# LFR_Body_Circuit.net
KiCad netlist of a schematic drawn in EasyEDA
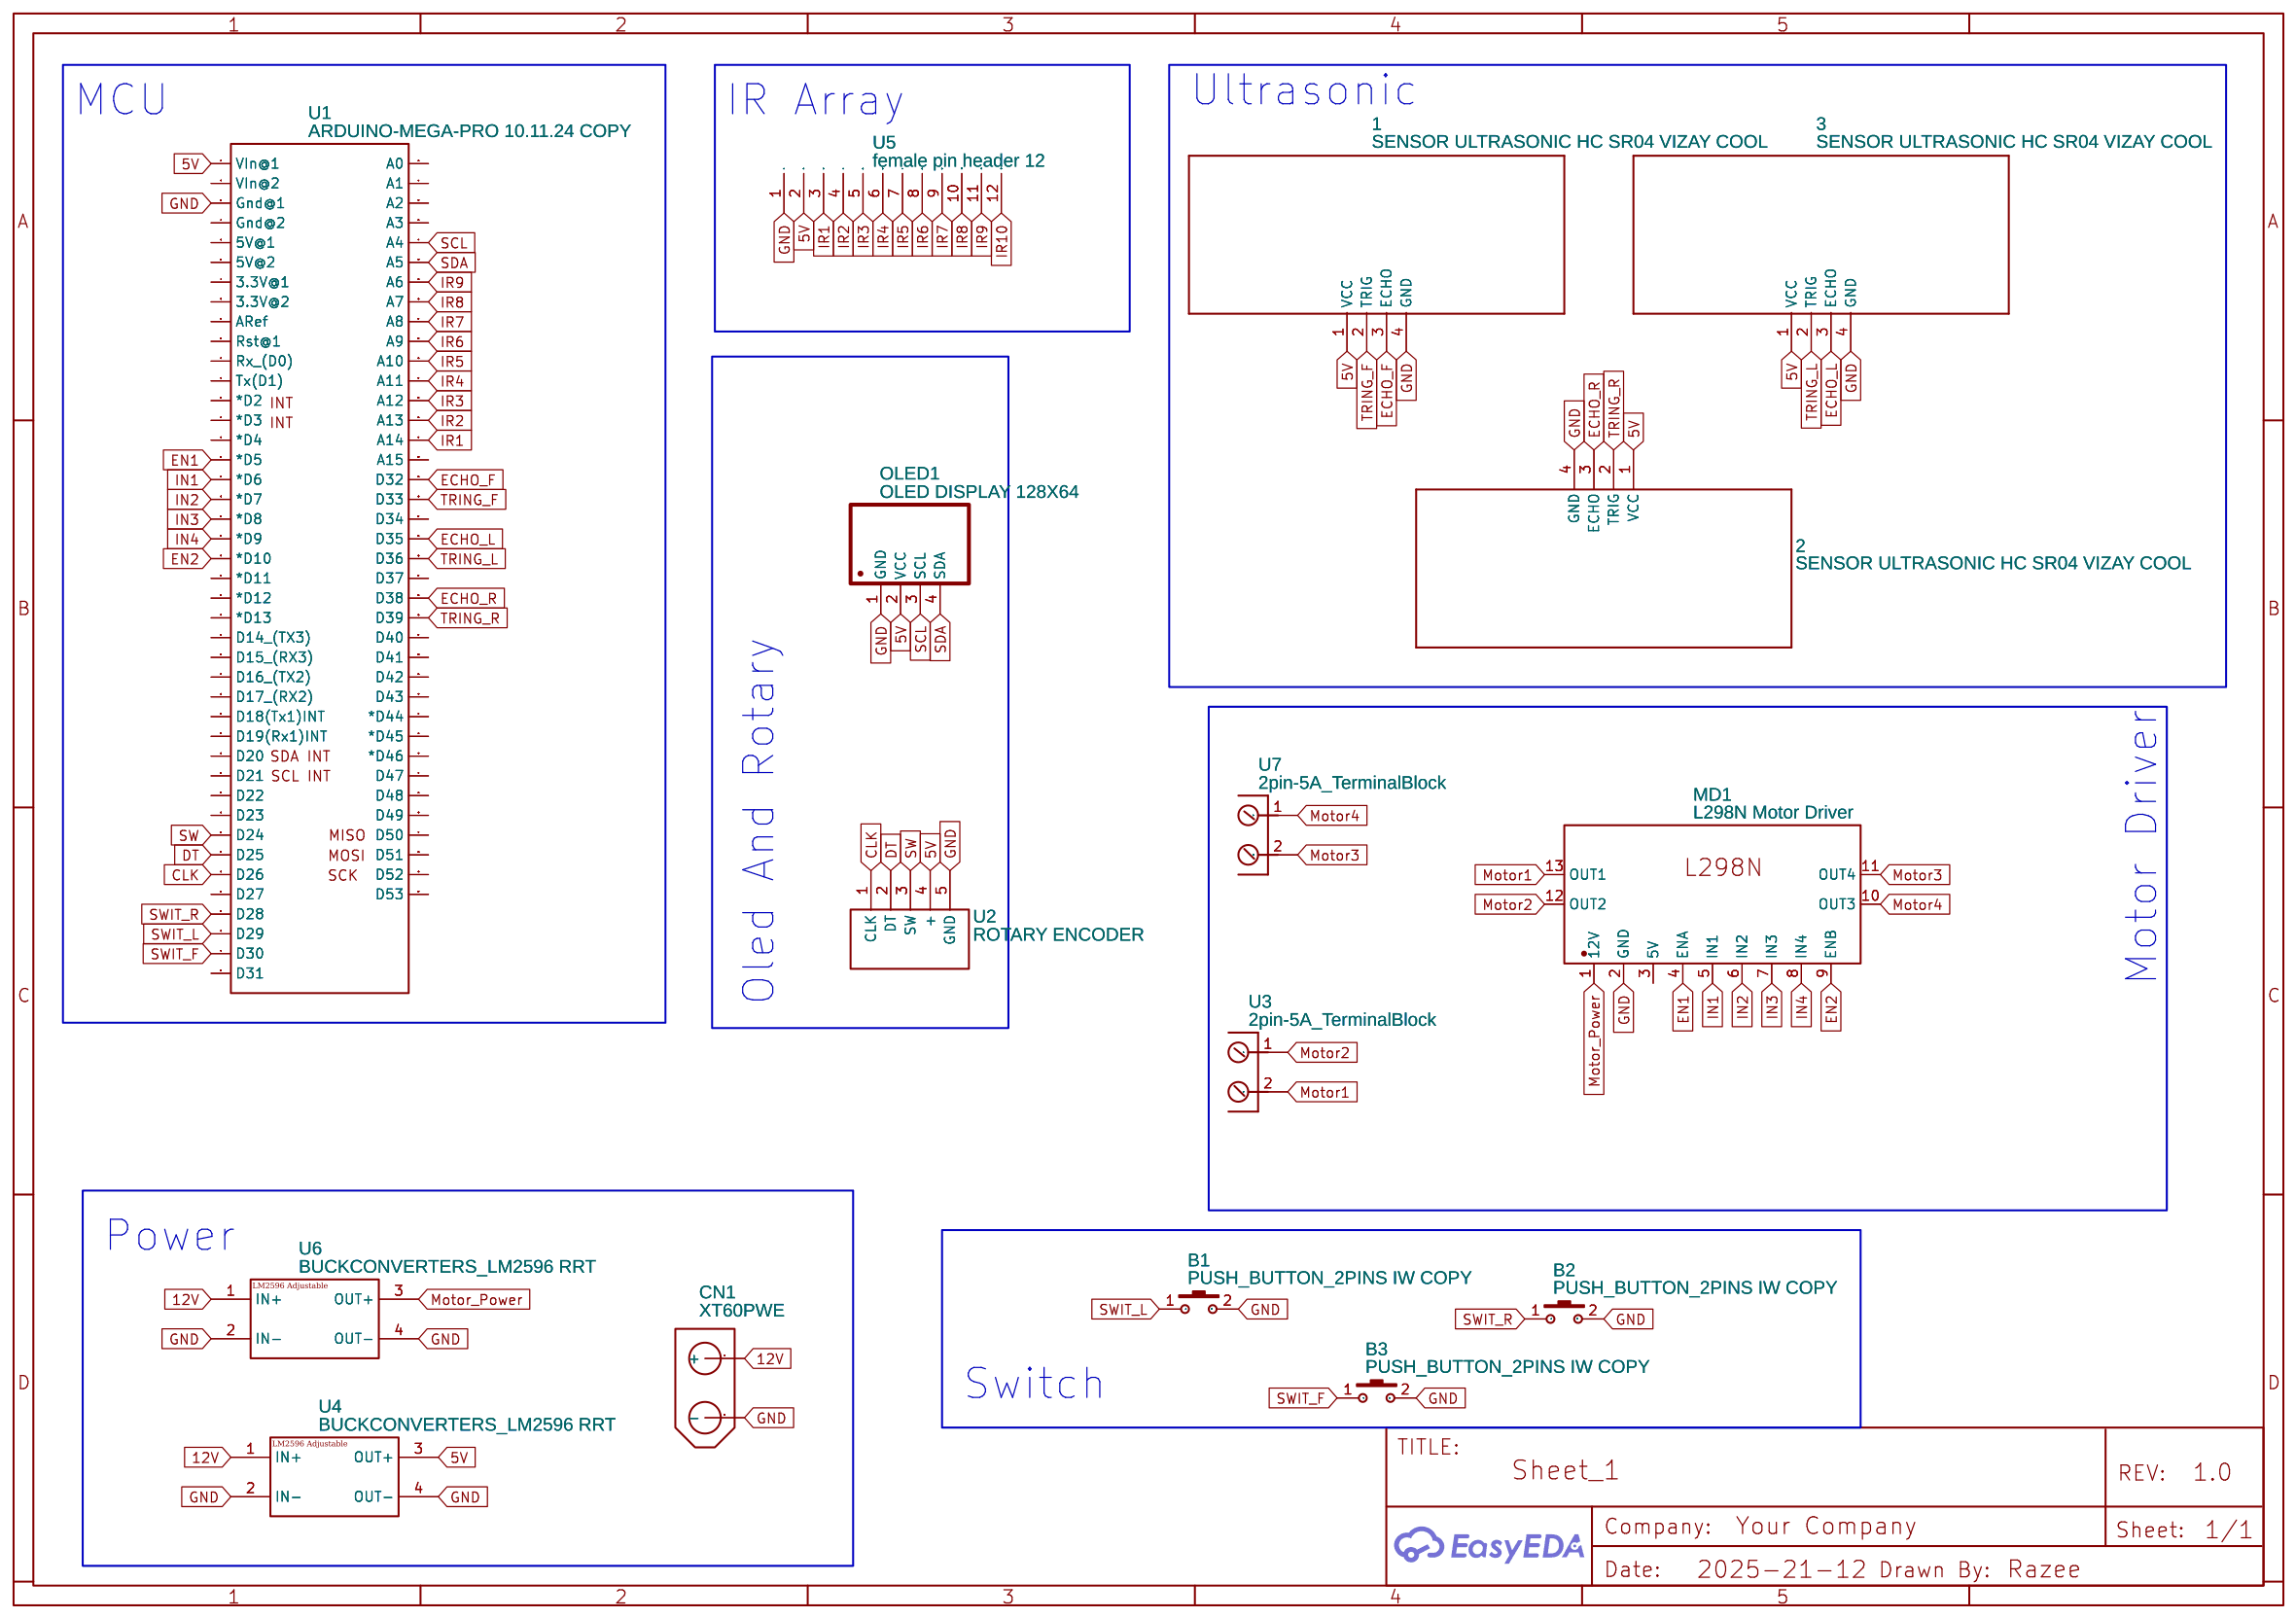
[diagram p0: schematic sheet]

(export (version "E")
  (design (tool "Eeschema 10.0.6"))
  (components
    (comp (ref "1")
      (value "SENSOR ULTRASONIC HC SR04 VIZAY COOL")
      (libsource (lib "") (part "SENSOR ULTRASONIC HC SR04 VIZAY COOL"))
    )
    (comp (ref "2")
      (value "SENSOR ULTRASONIC HC SR04 VIZAY COOL")
      (libsource (lib "") (part "SENSOR ULTRASONIC HC SR04 VIZAY COOL_1"))
    )
    (comp (ref "3")
      (value "SENSOR ULTRASONIC HC SR04 VIZAY COOL")
      (libsource (lib "") (part "SENSOR ULTRASONIC HC SR04 VIZAY COOL"))
    )
    (comp (ref "B1")
      (value "PUSH_BUTTON_2PINS IW COPY")
      (fields (field (name "Manufacturer Part") "PUSH_BUTTON_2Pini"))
      (libsource (lib "") (part "PUSH_BUTTON_2PINS IW COPY"))
    )
    (comp (ref "B2")
      (value "PUSH_BUTTON_2PINS IW COPY")
      (fields (field (name "Manufacturer Part") "PUSH_BUTTON_2Pini"))
      (libsource (lib "") (part "PUSH_BUTTON_2PINS IW COPY"))
    )
    (comp (ref "B3")
      (value "PUSH_BUTTON_2PINS IW COPY")
      (fields (field (name "Manufacturer Part") "PUSH_BUTTON_2Pini"))
      (libsource (lib "") (part "PUSH_BUTTON_2PINS IW COPY"))
    )
    (comp (ref "CN1")
      (value "XT60PWE")
      (fields (field (name "Manufacturer") "Changzhou Amass Elec"))
      (libsource (lib "") (part "XT60 COPY COPY"))
    )
    (comp (ref "MD1") (value "L298N Motor Driver") (libsource (lib "") (part "L298N Motor Driver")))
    (comp (ref "OLED1") (value "OLED DISPLAY 128X64") (libsource (lib "") (part "OLED DISPLAY 128X64")))
    (comp (ref "U1")
      (value "ARDUINO-MEGA-PRO 10.11.24 COPY")
      (fields (field (name "Manufacturer Part") "ARDUINO MEGA 2560 PRO EMBED"))
      (libsource (lib "") (part "ARDUINO-MEGA-PRO 10.11.24 COPY"))
    )
    (comp (ref "U2") (value "ROTARY ENCODER") (libsource (lib "") (part "ROTARY ENCODER")))
    (comp (ref "U3") (value "2pin-5A_TerminalBlock") (libsource (lib "") (part "2pin-5A_TerminalBlock")))
    (comp (ref "U4")
      (value "BUCKCONVERTERS_LM2596 RRT")
      (libsource (lib "") (part "BuckConverters_LM2596_Adj"))
    )
    (comp (ref "U5")
      (value "female pin header 12")
      (fields (field (name "Manufacturer Part") "New SchematicLib"))
      (libsource (lib "") (part "female pin header 12"))
    )
    (comp (ref "U6")
      (value "BUCKCONVERTERS_LM2596 RRT")
      (libsource (lib "") (part "BuckConverters_LM2596_Adj"))
    )
    (comp (ref "U7") (value "2pin-5A_TerminalBlock") (libsource (lib "") (part "2pin-5A_TerminalBlock")))
  )
  (nets
    (net (code "1") (name "5V") (class "Default")
      (node (ref "1") (pin "1") (pinfunction "VCC_1") (pintype "bidirectional"))
      (node (ref "2") (pin "1") (pinfunction "VCC_1") (pintype "bidirectional"))
      (node (ref "3") (pin "1") (pinfunction "VCC_1") (pintype "bidirectional"))
      (node (ref "OLED1") (pin "2") (pinfunction "VCC_2") (pintype "unspecified"))
      (node (ref "U1") (pin "1") (pinfunction "VIn@1_1") (pintype "unspecified"))
      (node (ref "U2") (pin "4") (pinfunction "+_4") (pintype "unspecified"))
      (node (ref "U4") (pin "3") (pinfunction "OUT+_3") (pintype "unspecified"))
      (node (ref "U5") (pin "2") (pinfunction "2_2") (pintype "unspecified"))
    )
    (net (code "2") (name "12V") (class "Default")
      (node (ref "CN1") (pin "1") (pinfunction "+_1") (pintype "unspecified"))
      (node (ref "U4") (pin "1") (pinfunction "IN+_1") (pintype "unspecified"))
      (node (ref "U6") (pin "1") (pinfunction "IN+_1") (pintype "unspecified"))
    )
    (net (code "3") (name "CLK") (class "Default")
      (node (ref "U1") (pin "37") (pinfunction "D26_37") (pintype "unspecified"))
      (node (ref "U2") (pin "1") (pinfunction "CLK_1") (pintype "unspecified"))
    )
    (net (code "4") (name "DT") (class "Default")
      (node (ref "U1") (pin "36") (pinfunction "D25_36") (pintype "unspecified"))
      (node (ref "U2") (pin "2") (pinfunction "DT_2") (pintype "unspecified"))
    )
    (net (code "5") (name "ECHO_F") (class "Default")
      (node (ref "1") (pin "3") (pinfunction "ECHO_3") (pintype "bidirectional"))
      (node (ref "U1") (pin "59") (pinfunction "D32_59") (pintype "unspecified"))
    )
    (net (code "6") (name "ECHO_L") (class "Default")
      (node (ref "3") (pin "3") (pinfunction "ECHO_3") (pintype "bidirectional"))
      (node (ref "U1") (pin "62") (pinfunction "D35_62") (pintype "unspecified"))
    )
    (net (code "7") (name "ECHO_R") (class "Default")
      (node (ref "2") (pin "3") (pinfunction "ECHO_3") (pintype "bidirectional"))
      (node (ref "U1") (pin "65") (pinfunction "D38_65") (pintype "unspecified"))
    )
    (net (code "8") (name "EN1") (class "Default")
      (node (ref "MD1") (pin "4") (pinfunction "ENA_4") (pintype "unspecified"))
      (node (ref "U1") (pin "16") (pinfunction "*D5_16") (pintype "unspecified"))
    )
    (net (code "9") (name "EN2") (class "Default")
      (node (ref "MD1") (pin "9") (pinfunction "ENB_9") (pintype "unspecified"))
      (node (ref "U1") (pin "21") (pinfunction "*D10_21") (pintype "unspecified"))
    )
    (net (code "10") (name "GND") (class "Default")
      (node (ref "1") (pin "4") (pinfunction "GND_4") (pintype "bidirectional"))
      (node (ref "2") (pin "4") (pinfunction "GND_4") (pintype "bidirectional"))
      (node (ref "3") (pin "4") (pinfunction "GND_4") (pintype "bidirectional"))
      (node (ref "B1") (pin "2") (pinfunction "2_2") (pintype "unspecified"))
      (node (ref "B2") (pin "2") (pinfunction "2_2") (pintype "unspecified"))
      (node (ref "B3") (pin "2") (pinfunction "2_2") (pintype "unspecified"))
      (node (ref "CN1") (pin "2") (pinfunction "-_2") (pintype "unspecified"))
      (node (ref "MD1") (pin "2") (pinfunction "GND_2") (pintype "unspecified"))
      (node (ref "OLED1") (pin "1") (pinfunction "GND_1") (pintype "unspecified"))
      (node (ref "U1") (pin "3") (pinfunction "Gnd@1_3") (pintype "unspecified"))
      (node (ref "U2") (pin "5") (pinfunction "GND_5") (pintype "unspecified"))
      (node (ref "U4") (pin "2") (pinfunction "IN-_2") (pintype "unspecified"))
      (node (ref "U4") (pin "4") (pinfunction "OUT-_4") (pintype "unspecified"))
      (node (ref "U5") (pin "1") (pinfunction "1_1") (pintype "unspecified"))
      (node (ref "U6") (pin "2") (pinfunction "IN-_2") (pintype "unspecified"))
      (node (ref "U6") (pin "4") (pinfunction "OUT-_4") (pintype "unspecified"))
    )
    (net (code "11") (name "IN1") (class "Default")
      (node (ref "MD1") (pin "5") (pinfunction "IN1_5") (pintype "unspecified"))
      (node (ref "U1") (pin "17") (pinfunction "*D6_17") (pintype "unspecified"))
    )
    (net (code "12") (name "IN2") (class "Default")
      (node (ref "MD1") (pin "6") (pinfunction "IN2_6") (pintype "unspecified"))
      (node (ref "U1") (pin "18") (pinfunction "*D7_18") (pintype "unspecified"))
    )
    (net (code "13") (name "IN3") (class "Default")
      (node (ref "MD1") (pin "7") (pinfunction "IN3_7") (pintype "unspecified"))
      (node (ref "U1") (pin "19") (pinfunction "*D8_19") (pintype "unspecified"))
    )
    (net (code "14") (name "IN4") (class "Default")
      (node (ref "MD1") (pin "8") (pinfunction "IN4_8") (pintype "unspecified"))
      (node (ref "U1") (pin "20") (pinfunction "*D9_20") (pintype "unspecified"))
    )
    (net (code "15") (name "IR1") (class "Default")
      (node (ref "U1") (pin "57") (pinfunction "A14_57") (pintype "unspecified"))
      (node (ref "U5") (pin "3") (pinfunction "3_3") (pintype "unspecified"))
    )
    (net (code "16") (name "IR2") (class "Default")
      (node (ref "U1") (pin "56") (pinfunction "A13_56") (pintype "unspecified"))
      (node (ref "U5") (pin "4") (pinfunction "4_4") (pintype "unspecified"))
    )
    (net (code "17") (name "IR3") (class "Default")
      (node (ref "U1") (pin "55") (pinfunction "A12_55") (pintype "unspecified"))
      (node (ref "U5") (pin "5") (pinfunction "5_5") (pintype "unspecified"))
    )
    (net (code "18") (name "IR4") (class "Default")
      (node (ref "U1") (pin "54") (pinfunction "A11_54") (pintype "unspecified"))
      (node (ref "U5") (pin "6") (pinfunction "6_6") (pintype "unspecified"))
    )
    (net (code "19") (name "IR5") (class "Default")
      (node (ref "U1") (pin "53") (pinfunction "A10_53") (pintype "unspecified"))
      (node (ref "U5") (pin "7") (pinfunction "7_7") (pintype "unspecified"))
    )
    (net (code "20") (name "IR6") (class "Default")
      (node (ref "U1") (pin "52") (pinfunction "A9_52") (pintype "unspecified"))
      (node (ref "U5") (pin "8") (pinfunction "8_8") (pintype "unspecified"))
    )
    (net (code "21") (name "IR7") (class "Default")
      (node (ref "U1") (pin "51") (pinfunction "A8_51") (pintype "unspecified"))
      (node (ref "U5") (pin "9") (pinfunction "9_9") (pintype "unspecified"))
    )
    (net (code "22") (name "IR8") (class "Default")
      (node (ref "U1") (pin "50") (pinfunction "A7_50") (pintype "unspecified"))
      (node (ref "U5") (pin "10") (pinfunction "10_10") (pintype "unspecified"))
    )
    (net (code "23") (name "IR9") (class "Default")
      (node (ref "U1") (pin "49") (pinfunction "A6_49") (pintype "unspecified"))
      (node (ref "U5") (pin "11") (pinfunction "11_11") (pintype "unspecified"))
    )
    (net (code "24") (name "IR10") (class "Default")
      (node (ref "U5") (pin "12") (pinfunction "12_12") (pintype "unspecified"))
    )
    (net (code "25") (name "Motor1") (class "Default")
      (node (ref "MD1") (pin "13") (pinfunction "OUT1_13") (pintype "unspecified"))
      (node (ref "U3") (pin "2") (pinfunction "2_2") (pintype "unspecified"))
    )
    (net (code "26") (name "Motor2") (class "Default")
      (node (ref "MD1") (pin "12") (pinfunction "OUT2_12") (pintype "unspecified"))
      (node (ref "U3") (pin "1") (pinfunction "1_1") (pintype "unspecified"))
    )
    (net (code "27") (name "Motor3") (class "Default")
      (node (ref "MD1") (pin "11") (pinfunction "OUT4_11") (pintype "unspecified"))
      (node (ref "U7") (pin "2") (pinfunction "2_2") (pintype "unspecified"))
    )
    (net (code "28") (name "Motor4") (class "Default")
      (node (ref "MD1") (pin "10") (pinfunction "OUT3_10") (pintype "unspecified"))
      (node (ref "U7") (pin "1") (pinfunction "1_1") (pintype "unspecified"))
    )
    (net (code "29") (name "Motor_Power") (class "Default")
      (node (ref "MD1") (pin "1") (pinfunction "12V_1") (pintype "unspecified"))
      (node (ref "U6") (pin "3") (pinfunction "OUT+_3") (pintype "unspecified"))
    )
    (net (code "30") (name "SCL") (class "Default")
      (node (ref "OLED1") (pin "3") (pinfunction "SCL_3") (pintype "unspecified"))
      (node (ref "U1") (pin "47") (pinfunction "A4_47") (pintype "unspecified"))
    )
    (net (code "31") (name "SDA") (class "Default")
      (node (ref "OLED1") (pin "4") (pinfunction "SDA_4") (pintype "unspecified"))
      (node (ref "U1") (pin "48") (pinfunction "A5_48") (pintype "unspecified"))
    )
    (net (code "32") (name "SW") (class "Default")
      (node (ref "U1") (pin "35") (pinfunction "D24_35") (pintype "unspecified"))
      (node (ref "U2") (pin "3") (pinfunction "SW_3") (pintype "unspecified"))
    )
    (net (code "33") (name "SWIT_F") (class "Default")
      (node (ref "B3") (pin "1") (pinfunction "1_1") (pintype "unspecified"))
      (node (ref "U1") (pin "41") (pinfunction "D30_41") (pintype "unspecified"))
    )
    (net (code "34") (name "SWIT_L") (class "Default")
      (node (ref "B1") (pin "1") (pinfunction "1_1") (pintype "unspecified"))
      (node (ref "U1") (pin "40") (pinfunction "D29_40") (pintype "unspecified"))
    )
    (net (code "35") (name "SWIT_R") (class "Default")
      (node (ref "B2") (pin "1") (pinfunction "1_1") (pintype "unspecified"))
      (node (ref "U1") (pin "39") (pinfunction "D28_39") (pintype "unspecified"))
    )
    (net (code "36") (name "TRING_F") (class "Default")
      (node (ref "1") (pin "2") (pinfunction "TRIG_2") (pintype "bidirectional"))
      (node (ref "U1") (pin "60") (pinfunction "D33_60") (pintype "unspecified"))
    )
    (net (code "37") (name "TRING_L") (class "Default")
      (node (ref "3") (pin "2") (pinfunction "TRIG_2") (pintype "bidirectional"))
      (node (ref "U1") (pin "63") (pinfunction "D36_63") (pintype "unspecified"))
    )
    (net (code "38") (name "TRING_R") (class "Default")
      (node (ref "2") (pin "2") (pinfunction "TRIG_2") (pintype "bidirectional"))
      (node (ref "U1") (pin "66") (pinfunction "D39_66") (pintype "unspecified"))
    )
    (net (code "39") (name "unconnected-(MD1-5V-Pad3)") (class "Default")
      (node (ref "MD1") (pin "3") (pinfunction "5V_3") (pintype "unspecified"))
    )
    (net (code "40") (name "unconnected-(U1-*D2-Pad13)") (class "Default")
      (node (ref "U1") (pin "13") (pinfunction "*D2_13") (pintype "unspecified"))
    )
    (net (code "41") (name "unconnected-(U1-*D3-Pad14)") (class "Default")
      (node (ref "U1") (pin "14") (pinfunction "*D3_14") (pintype "unspecified"))
    )
    (net (code "42") (name "unconnected-(U1-*D4-Pad15)") (class "Default")
      (node (ref "U1") (pin "15") (pinfunction "*D4_15") (pintype "unspecified"))
    )
    (net (code "43") (name "unconnected-(U1-*D11-Pad22)") (class "Default")
      (node (ref "U1") (pin "22") (pinfunction "*D11_22") (pintype "unspecified"))
    )
    (net (code "44") (name "unconnected-(U1-*D12-Pad23)") (class "Default")
      (node (ref "U1") (pin "23") (pinfunction "*D12_23") (pintype "unspecified"))
    )
    (net (code "45") (name "unconnected-(U1-*D13-Pad24)") (class "Default")
      (node (ref "U1") (pin "24") (pinfunction "*D13_24") (pintype "unspecified"))
    )
    (net (code "46") (name "unconnected-(U1-*D44-Pad71)") (class "Default")
      (node (ref "U1") (pin "71") (pinfunction "*D44_71") (pintype "unspecified"))
    )
    (net (code "47") (name "unconnected-(U1-*D45-Pad72)") (class "Default")
      (node (ref "U1") (pin "72") (pinfunction "*D45_72") (pintype "unspecified"))
    )
    (net (code "48") (name "unconnected-(U1-*D46-Pad73)") (class "Default")
      (node (ref "U1") (pin "73") (pinfunction "*D46_73") (pintype "unspecified"))
    )
    (net (code "49") (name "unconnected-(U1-3.3V@1-Pad7)") (class "Default")
      (node (ref "U1") (pin "7") (pinfunction "3.3V@1_7") (pintype "unspecified"))
    )
    (net (code "50") (name "unconnected-(U1-3.3V@2-Pad8)") (class "Default")
      (node (ref "U1") (pin "8") (pinfunction "3.3V@2_8") (pintype "unspecified"))
    )
    (net (code "51") (name "unconnected-(U1-5V@1-Pad5)") (class "Default")
      (node (ref "U1") (pin "5") (pinfunction "5V@1_5") (pintype "unspecified"))
    )
    (net (code "52") (name "unconnected-(U1-5V@2-Pad6)") (class "Default")
      (node (ref "U1") (pin "6") (pinfunction "5V@2_6") (pintype "unspecified"))
    )
    (net (code "53") (name "unconnected-(U1-A0-Pad43)") (class "Default")
      (node (ref "U1") (pin "43") (pinfunction "A0_43") (pintype "unspecified"))
    )
    (net (code "54") (name "unconnected-(U1-A1-Pad44)") (class "Default")
      (node (ref "U1") (pin "44") (pinfunction "A1_44") (pintype "unspecified"))
    )
    (net (code "55") (name "unconnected-(U1-A2-Pad45)") (class "Default")
      (node (ref "U1") (pin "45") (pinfunction "A2_45") (pintype "unspecified"))
    )
    (net (code "56") (name "unconnected-(U1-A3-Pad46)") (class "Default")
      (node (ref "U1") (pin "46") (pinfunction "A3_46") (pintype "unspecified"))
    )
    (net (code "57") (name "unconnected-(U1-A15-Pad58)") (class "Default")
      (node (ref "U1") (pin "58") (pinfunction "A15_58") (pintype "unspecified"))
    )
    (net (code "58") (name "unconnected-(U1-ARef-Pad9)") (class "Default")
      (node (ref "U1") (pin "9") (pinfunction "ARef_9") (pintype "unspecified"))
    )
    (net (code "59") (name "unconnected-(U1-D14_(TX3)-Pad25)") (class "Default")
      (node (ref "U1") (pin "25") (pinfunction "D14_(TX3)_25") (pintype "unspecified"))
    )
    (net (code "60") (name "unconnected-(U1-D15_(RX3)-Pad26)") (class "Default")
      (node (ref "U1") (pin "26") (pinfunction "D15_(RX3)_26") (pintype "unspecified"))
    )
    (net (code "61") (name "unconnected-(U1-D16_(TX2)-Pad27)") (class "Default")
      (node (ref "U1") (pin "27") (pinfunction "D16_(TX2)_27") (pintype "unspecified"))
    )
    (net (code "62") (name "unconnected-(U1-D17_(RX2)-Pad28)") (class "Default")
      (node (ref "U1") (pin "28") (pinfunction "D17_(RX2)_28") (pintype "unspecified"))
    )
    (net (code "63") (name "unconnected-(U1-D18(Tx1)INT-Pad29)") (class "Default")
      (node (ref "U1") (pin "29") (pinfunction "D18(Tx1)INT_29") (pintype "unspecified"))
    )
    (net (code "64") (name "unconnected-(U1-D19(Rx1)INT-Pad30)") (class "Default")
      (node (ref "U1") (pin "30") (pinfunction "D19(Rx1)INT_30") (pintype "unspecified"))
    )
    (net (code "65") (name "unconnected-(U1-D20-Pad31)") (class "Default")
      (node (ref "U1") (pin "31") (pinfunction "D20_31") (pintype "unspecified"))
    )
    (net (code "66") (name "unconnected-(U1-D21-Pad32)") (class "Default")
      (node (ref "U1") (pin "32") (pinfunction "D21_32") (pintype "unspecified"))
    )
    (net (code "67") (name "unconnected-(U1-D22-Pad33)") (class "Default")
      (node (ref "U1") (pin "33") (pinfunction "D22_33") (pintype "unspecified"))
    )
    (net (code "68") (name "unconnected-(U1-D23-Pad34)") (class "Default")
      (node (ref "U1") (pin "34") (pinfunction "D23_34") (pintype "unspecified"))
    )
    (net (code "69") (name "unconnected-(U1-D27-Pad38)") (class "Default")
      (node (ref "U1") (pin "38") (pinfunction "D27_38") (pintype "unspecified"))
    )
    (net (code "70") (name "unconnected-(U1-D31-Pad42)") (class "Default")
      (node (ref "U1") (pin "42") (pinfunction "D31_42") (pintype "unspecified"))
    )
    (net (code "71") (name "unconnected-(U1-D34-Pad61)") (class "Default")
      (node (ref "U1") (pin "61") (pinfunction "D34_61") (pintype "unspecified"))
    )
    (net (code "72") (name "unconnected-(U1-D37-Pad64)") (class "Default")
      (node (ref "U1") (pin "64") (pinfunction "D37_64") (pintype "unspecified"))
    )
    (net (code "73") (name "unconnected-(U1-D40-Pad67)") (class "Default")
      (node (ref "U1") (pin "67") (pinfunction "D40_67") (pintype "unspecified"))
    )
    (net (code "74") (name "unconnected-(U1-D41-Pad68)") (class "Default")
      (node (ref "U1") (pin "68") (pinfunction "D41_68") (pintype "unspecified"))
    )
    (net (code "75") (name "unconnected-(U1-D42-Pad69)") (class "Default")
      (node (ref "U1") (pin "69") (pinfunction "D42_69") (pintype "unspecified"))
    )
    (net (code "76") (name "unconnected-(U1-D43-Pad70)") (class "Default")
      (node (ref "U1") (pin "70") (pinfunction "D43_70") (pintype "unspecified"))
    )
    (net (code "77") (name "unconnected-(U1-D47-Pad74)") (class "Default")
      (node (ref "U1") (pin "74") (pinfunction "D47_74") (pintype "unspecified"))
    )
    (net (code "78") (name "unconnected-(U1-D48-Pad75)") (class "Default")
      (node (ref "U1") (pin "75") (pinfunction "D48_75") (pintype "unspecified"))
    )
    (net (code "79") (name "unconnected-(U1-D49-Pad76)") (class "Default")
      (node (ref "U1") (pin "76") (pinfunction "D49_76") (pintype "unspecified"))
    )
    (net (code "80") (name "unconnected-(U1-D50-Pad77)") (class "Default")
      (node (ref "U1") (pin "77") (pinfunction "D50_77") (pintype "unspecified"))
    )
    (net (code "81") (name "unconnected-(U1-D51-Pad78)") (class "Default")
      (node (ref "U1") (pin "78") (pinfunction "D51_78") (pintype "unspecified"))
    )
    (net (code "82") (name "unconnected-(U1-D52-Pad79)") (class "Default")
      (node (ref "U1") (pin "79") (pinfunction "D52_79") (pintype "unspecified"))
    )
    (net (code "83") (name "unconnected-(U1-D53-Pad80)") (class "Default")
      (node (ref "U1") (pin "80") (pinfunction "D53_80") (pintype "unspecified"))
    )
    (net (code "84") (name "unconnected-(U1-Gnd@2-Pad4)") (class "Default")
      (node (ref "U1") (pin "4") (pinfunction "Gnd@2_4") (pintype "unspecified"))
    )
    (net (code "85") (name "unconnected-(U1-Rst@1-Pad10)") (class "Default")
      (node (ref "U1") (pin "10") (pinfunction "Rst@1_10") (pintype "unspecified"))
    )
    (net (code "86") (name "unconnected-(U1-Rx_(D0)-Pad11)") (class "Default")
      (node (ref "U1") (pin "11") (pinfunction "Rx_(D0)_11") (pintype "unspecified"))
    )
    (net (code "87") (name "unconnected-(U1-Tx(D1)-Pad12)") (class "Default")
      (node (ref "U1") (pin "12") (pinfunction "Tx(D1)_12") (pintype "unspecified"))
    )
    (net (code "88") (name "unconnected-(U1-VIn@2-Pad2)") (class "Default")
      (node (ref "U1") (pin "2") (pinfunction "VIn@2_2") (pintype "unspecified"))
    )
  )
)
